# Power.net
KiCad netlist of a schematic drawn in Altium Designer
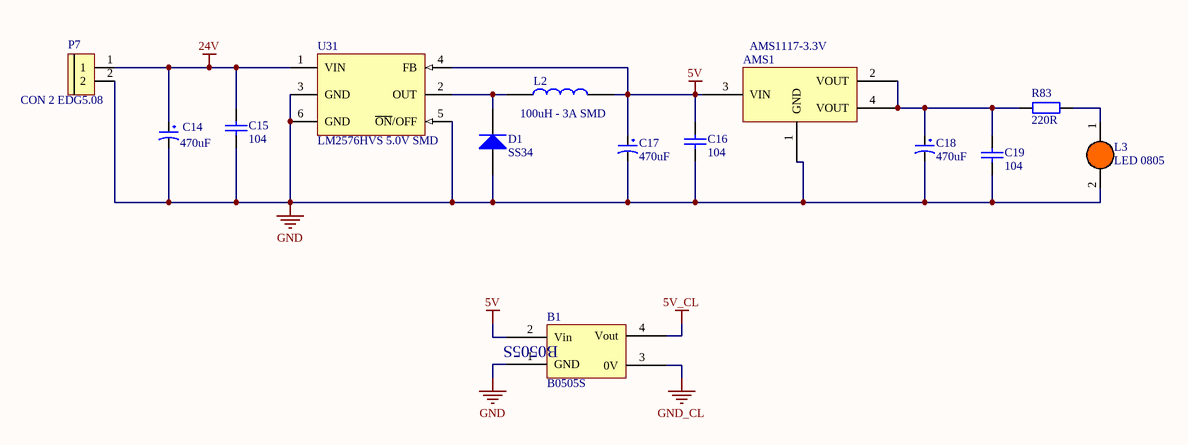
[diagram p0: Power.SchDoc]

(export (version "E")
  (design (tool "Eeschema 10.0.6"))
  (components
    (comp (ref "AMS1")
      (value "AMS1117-3.3V")
      (footprint "SOT223")
      (description "Dán")
      (libsource (lib "Altium_Lib_by_KhueNguyenCreator") (part "AMS1117 SMD"))
    )
    (comp (ref "B1")
      (value "B0505S")
      (footprint "B0505S")
      (description "Cắm")
      (libsource (lib "Altium_Lib_by_KhueNguyenCreator") (part "B0505S"))
    )
    (comp (ref "C14")
      (value "470uF")
      (footprint "tu hoa 10mm")
      (description "Cắm")
      (libsource (lib "Altium_Lib_by_KhueNguyenCreator") (part "Tu Hoa 470uF 50V 10x17"))
    )
    (comp (ref "C15")
      (value "104")
      (footprint "tu 0805")
      (description "Dán")
      (libsource (lib "Altium_Lib_by_KhueNguyenCreator") (part "Tu 0805 104 50V 10%"))
    )
    (comp (ref "C16")
      (value "104")
      (footprint "tu 0805")
      (description "Dán")
      (libsource (lib "Altium_Lib_by_KhueNguyenCreator") (part "Tu 0805 104 50V 10%"))
    )
    (comp (ref "C17")
      (value "470uF")
      (footprint "tu hoa 8mm")
      (description "Cắm")
      (libsource (lib "Altium_Lib_by_KhueNguyenCreator") (part "Tu Hoa 470uF 16V 8x11"))
    )
    (comp (ref "C18")
      (value "470uF")
      (footprint "tu hoa 8mm")
      (description "Cắm")
      (libsource (lib "Altium_Lib_by_KhueNguyenCreator") (part "Tu Hoa 470uF 16V 8x11"))
    )
    (comp (ref "C19")
      (value "104")
      (footprint "tu 0805")
      (description "Dán")
      (libsource (lib "Altium_Lib_by_KhueNguyenCreator") (part "Tu 0805 104 50V 10%"))
    )
    (comp (ref "D1")
      (value "SS34")
      (footprint "DIODE SMA")
      (description "Dán")
      (libsource (lib "Altium_Lib_by_KhueNguyenCreator") (part "Diode SS34 ( 1N5822 )"))
    )
    (comp (ref "L2")
      (value "100uH - 3A SMD")
      (footprint "Cuon Cam 12x12x10")
      (description "Dán")
      (libsource (lib "Altium_Lib_by_KhueNguyenCreator") (part "CUON CAM 100uH SMD"))
    )
    (comp (ref "L3")
      (value "LED 0805")
      (footprint "LED-0805-Orange")
      (description "Dán")
      (libsource (lib "Altium_Lib_by_KhueNguyenCreator") (part "LED 0805 Cam"))
    )
    (comp (ref "P7")
      (value "CON 2 EDG5.08")
      (footprint "CON 2 2EDG5.08")
      (description "Cắm")
      (libsource (lib "Altium_Lib_by_KhueNguyenCreator") (part "CON 2 EDG5.08"))
    )
    (comp (ref "R83")
      (value "220R")
      (footprint "tro smd 0805")
      (description "Dán")
      (libsource (lib "Altium_Lib_by_KhueNguyenCreator") (part "Tro 0805 5% 220R"))
    )
    (comp (ref "U31")
      (value "LM2576HVS 5.0V SMD")
      (footprint "TO263-5")
      (description "Dán")
      (libsource (lib "Altium_Lib_by_KhueNguyenCreator") (part "LM2576HVS 5.0V SMD"))
    )
  )
  (nets
    (net (code "1") (name "5V") (class "Default")
      (node (ref "AMS1") (pin "3") (pinfunction "VIN_3") (pintype "passive"))
      (node (ref "B1") (pin "2") (pinfunction "Vin_2") (pintype "passive"))
      (node (ref "C16") (pin "1") (pinfunction "1_1") (pintype "passive"))
      (node (ref "C17") (pin "1") (pinfunction "1_1") (pintype "passive"))
      (node (ref "L2") (pin "2") (pinfunction "2_2") (pintype "passive"))
      (node (ref "U31") (pin "4") (pinfunction "FB_4") (pintype "input"))
    )
    (net (code "2") (name "5V_CL") (class "Default")
      (node (ref "B1") (pin "4") (pinfunction "Vout_4") (pintype "passive"))
    )
    (net (code "3") (name "24V") (class "Default")
      (node (ref "C14") (pin "1") (pinfunction "1_1") (pintype "passive"))
      (node (ref "C15") (pin "2") (pinfunction "2_2") (pintype "passive"))
      (node (ref "P7") (pin "1") (pinfunction "1_1") (pintype "passive"))
      (node (ref "U31") (pin "1") (pinfunction "VIN_1") (pintype "power_in"))
    )
    (net (code "4") (name "GND") (class "Default")
      (node (ref "AMS1") (pin "1") (pinfunction "GND_1") (pintype "passive"))
      (node (ref "B1") (pin "1") (pinfunction "GND_1") (pintype "passive"))
      (node (ref "C14") (pin "2") (pinfunction "2_2") (pintype "passive"))
      (node (ref "C15") (pin "1") (pinfunction "1_1") (pintype "passive"))
      (node (ref "C16") (pin "2") (pinfunction "2_2") (pintype "passive"))
      (node (ref "C17") (pin "2") (pinfunction "2_2") (pintype "passive"))
      (node (ref "C18") (pin "2") (pinfunction "2_2") (pintype "passive"))
      (node (ref "C19") (pin "2") (pinfunction "2_2") (pintype "passive"))
      (node (ref "D1") (pin "1") (pinfunction "A_1") (pintype "passive"))
      (node (ref "L3") (pin "2") (pinfunction "K_2") (pintype "passive"))
      (node (ref "P7") (pin "2") (pinfunction "2_2") (pintype "passive"))
      (node (ref "U31") (pin "3") (pinfunction "GND_3") (pintype "power_in"))
      (node (ref "U31") (pin "5") (pinfunction "~{ON}/OFF_5") (pintype "input"))
      (node (ref "U31") (pin "6") (pinfunction "GND_6") (pintype "passive"))
    )
    (net (code "5") (name "GND_CL") (class "Default")
      (node (ref "B1") (pin "3") (pinfunction "0V_3") (pintype "passive"))
    )
    (net (code "6") (name "Net-(AMS1-VOUT-Pad2)") (class "Default")
      (node (ref "AMS1") (pin "2") (pinfunction "VOUT_2") (pintype "passive"))
      (node (ref "AMS1") (pin "4") (pinfunction "VOUT_4") (pintype "passive"))
      (node (ref "C18") (pin "1") (pinfunction "1_1") (pintype "passive"))
      (node (ref "C19") (pin "1") (pinfunction "1_1") (pintype "passive"))
      (node (ref "R83") (pin "1") (pinfunction "1_1") (pintype "passive"))
    )
    (net (code "7") (name "Net-(D1-K)") (class "Default")
      (node (ref "D1") (pin "2") (pinfunction "K_2") (pintype "passive"))
      (node (ref "L2") (pin "1") (pinfunction "1_1") (pintype "passive"))
      (node (ref "U31") (pin "2") (pinfunction "OUT_2") (pintype "power_in"))
    )
    (net (code "8") (name "Net-(L3-A)") (class "Default")
      (node (ref "L3") (pin "1") (pinfunction "A_1") (pintype "passive"))
      (node (ref "R83") (pin "2") (pinfunction "2_2") (pintype "passive"))
    )
  )
)
